# Circuito_Fonte.net
KiCad netlist of a schematic drawn in EAGLE
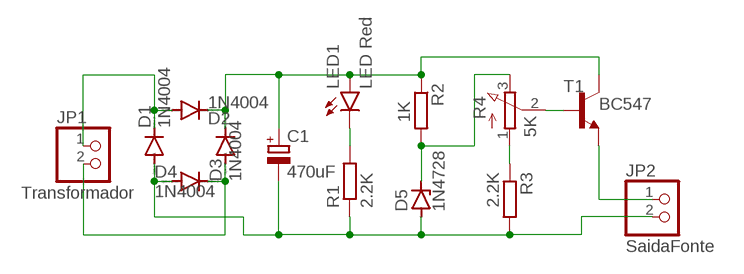
[diagram p0: schematic, sheet 2]

(export (version "E")
  (design (tool "Eeschema 10.0.6"))
  (components
    (comp (ref "C1")
      (value "470uF")
      (footprint "eagle-import:E5-10,5")
      (libsource (lib "eagle-import") (part "CPOL-EUE5-10.5"))
    )
    (comp (ref "D1")
      (value "1N4004")
      (footprint "eagle-import:DO41-10")
      (libsource (lib "eagle-import") (part "1N4004"))
    )
    (comp (ref "D2")
      (value "1N4004")
      (footprint "eagle-import:DO41-10")
      (libsource (lib "eagle-import") (part "1N4004"))
    )
    (comp (ref "D3")
      (value "1N4004")
      (footprint "eagle-import:DO41-10")
      (libsource (lib "eagle-import") (part "1N4004"))
    )
    (comp (ref "D4")
      (value "1N4004")
      (footprint "eagle-import:DO41-10")
      (libsource (lib "eagle-import") (part "1N4004"))
    )
    (comp (ref "D5")
      (value "1N4728")
      (footprint "eagle-import:DO41Z10")
      (libsource (lib "eagle-import") (part "1N4728"))
    )
    (comp (ref "JP1")
      (value "Transformador")
      (footprint "eagle-import:1X02")
      (libsource (lib "eagle-import") (part "PINHD-1X2"))
    )
    (comp (ref "JP2")
      (value "SaidaFonte")
      (footprint "eagle-import:1X02")
      (libsource (lib "eagle-import") (part "PINHD-1X2"))
    )
    (comp (ref "LED1")
      (value "LED Red")
      (footprint "eagle-import:LED5MM")
      (libsource (lib "eagle-import") (part "LED5MM"))
    )
    (comp (ref "R1")
      (value "2.2K")
      (footprint "eagle-import:0204_7")
      (libsource (lib "eagle-import") (part "R-EU_0204/7"))
    )
    (comp (ref "R2")
      (value "1K")
      (footprint "eagle-import:0204_7")
      (libsource (lib "eagle-import") (part "R-EU_0204/7"))
    )
    (comp (ref "R3")
      (value "2.2K")
      (footprint "eagle-import:0204_7")
      (libsource (lib "eagle-import") (part "R-EU_0204/7"))
    )
    (comp (ref "R4")
      (value "5K")
      (footprint "eagle-import:3RP_1610N")
      (libsource (lib "eagle-import") (part "3RP/1610N"))
    )
    (comp (ref "T1")
      (value "BC547")
      (footprint "eagle-import:TO92")
      (libsource (lib "eagle-import") (part "BC547"))
    )
  )
  (nets
    (net (code "1") (name "Net-(C1-Pad-)") (class "Default")
      (node (ref "C1") (pin "-") (pinfunction "-_-") (pintype "passive"))
      (node (ref "D1") (pin "A") (pinfunction "A_A") (pintype "passive"))
      (node (ref "D4") (pin "A") (pinfunction "A_A") (pintype "passive"))
      (node (ref "D5") (pin "A") (pinfunction "A_A") (pintype "passive"))
      (node (ref "JP2") (pin "2") (pinfunction "2_2") (pintype "passive"))
      (node (ref "R1") (pin "1") (pinfunction "1_1") (pintype "passive"))
      (node (ref "R3") (pin "2") (pinfunction "2_2") (pintype "passive"))
    )
    (net (code "2") (name "Net-(D1-PadC)") (class "Default")
      (node (ref "D1") (pin "C") (pinfunction "C_C") (pintype "passive"))
      (node (ref "D2") (pin "A") (pinfunction "A_A") (pintype "passive"))
      (node (ref "JP1") (pin "1") (pinfunction "1_1") (pintype "passive"))
    )
    (net (code "3") (name "Net-(D3-PadA)") (class "Default")
      (node (ref "D3") (pin "A") (pinfunction "A_A") (pintype "passive"))
      (node (ref "D4") (pin "C") (pinfunction "C_C") (pintype "passive"))
      (node (ref "JP1") (pin "2") (pinfunction "2_2") (pintype "passive"))
    )
    (net (code "4") (name "Net-(LED1-C)") (class "Default")
      (node (ref "LED1") (pin "K") (pinfunction "C_K") (pintype "passive"))
      (node (ref "R1") (pin "2") (pinfunction "2_2") (pintype "passive"))
    )
    (net (code "5") (name "Net-(R4-A)") (class "Default")
      (node (ref "R3") (pin "1") (pinfunction "1_1") (pintype "passive"))
      (node (ref "R4") (pin "1") (pinfunction "A_1") (pintype "passive"))
    )
    (net (code "6") (name "Net-(R4-E)") (class "Default")
      (node (ref "D5") (pin "C") (pinfunction "C_C") (pintype "passive"))
      (node (ref "R2") (pin "2") (pinfunction "2_2") (pintype "passive"))
      (node (ref "R4") (pin "3") (pinfunction "E_3") (pintype "passive"))
    )
    (net (code "7") (name "Net-(R4-S)") (class "Default")
      (node (ref "R4") (pin "2") (pinfunction "S_2") (pintype "passive"))
      (node (ref "T1") (pin "2") (pinfunction "B_2") (pintype "passive"))
    )
    (net (code "8") (name "Net-(T1-C)") (class "Default")
      (node (ref "C1") (pin "+") (pinfunction "+_+") (pintype "passive"))
      (node (ref "D2") (pin "C") (pinfunction "C_C") (pintype "passive"))
      (node (ref "D3") (pin "C") (pinfunction "C_C") (pintype "passive"))
      (node (ref "LED1") (pin "A") (pinfunction "A_A") (pintype "passive"))
      (node (ref "R2") (pin "1") (pinfunction "1_1") (pintype "passive"))
      (node (ref "T1") (pin "3") (pinfunction "C_3") (pintype "passive"))
    )
    (net (code "9") (name "Net-(T1-E)") (class "Default")
      (node (ref "JP2") (pin "1") (pinfunction "1_1") (pintype "passive"))
      (node (ref "T1") (pin "1") (pinfunction "E_1") (pintype "passive"))
    )
  )
)
